# P07-LCD.net
KiCad netlist of a schematic drawn in Altium Designer
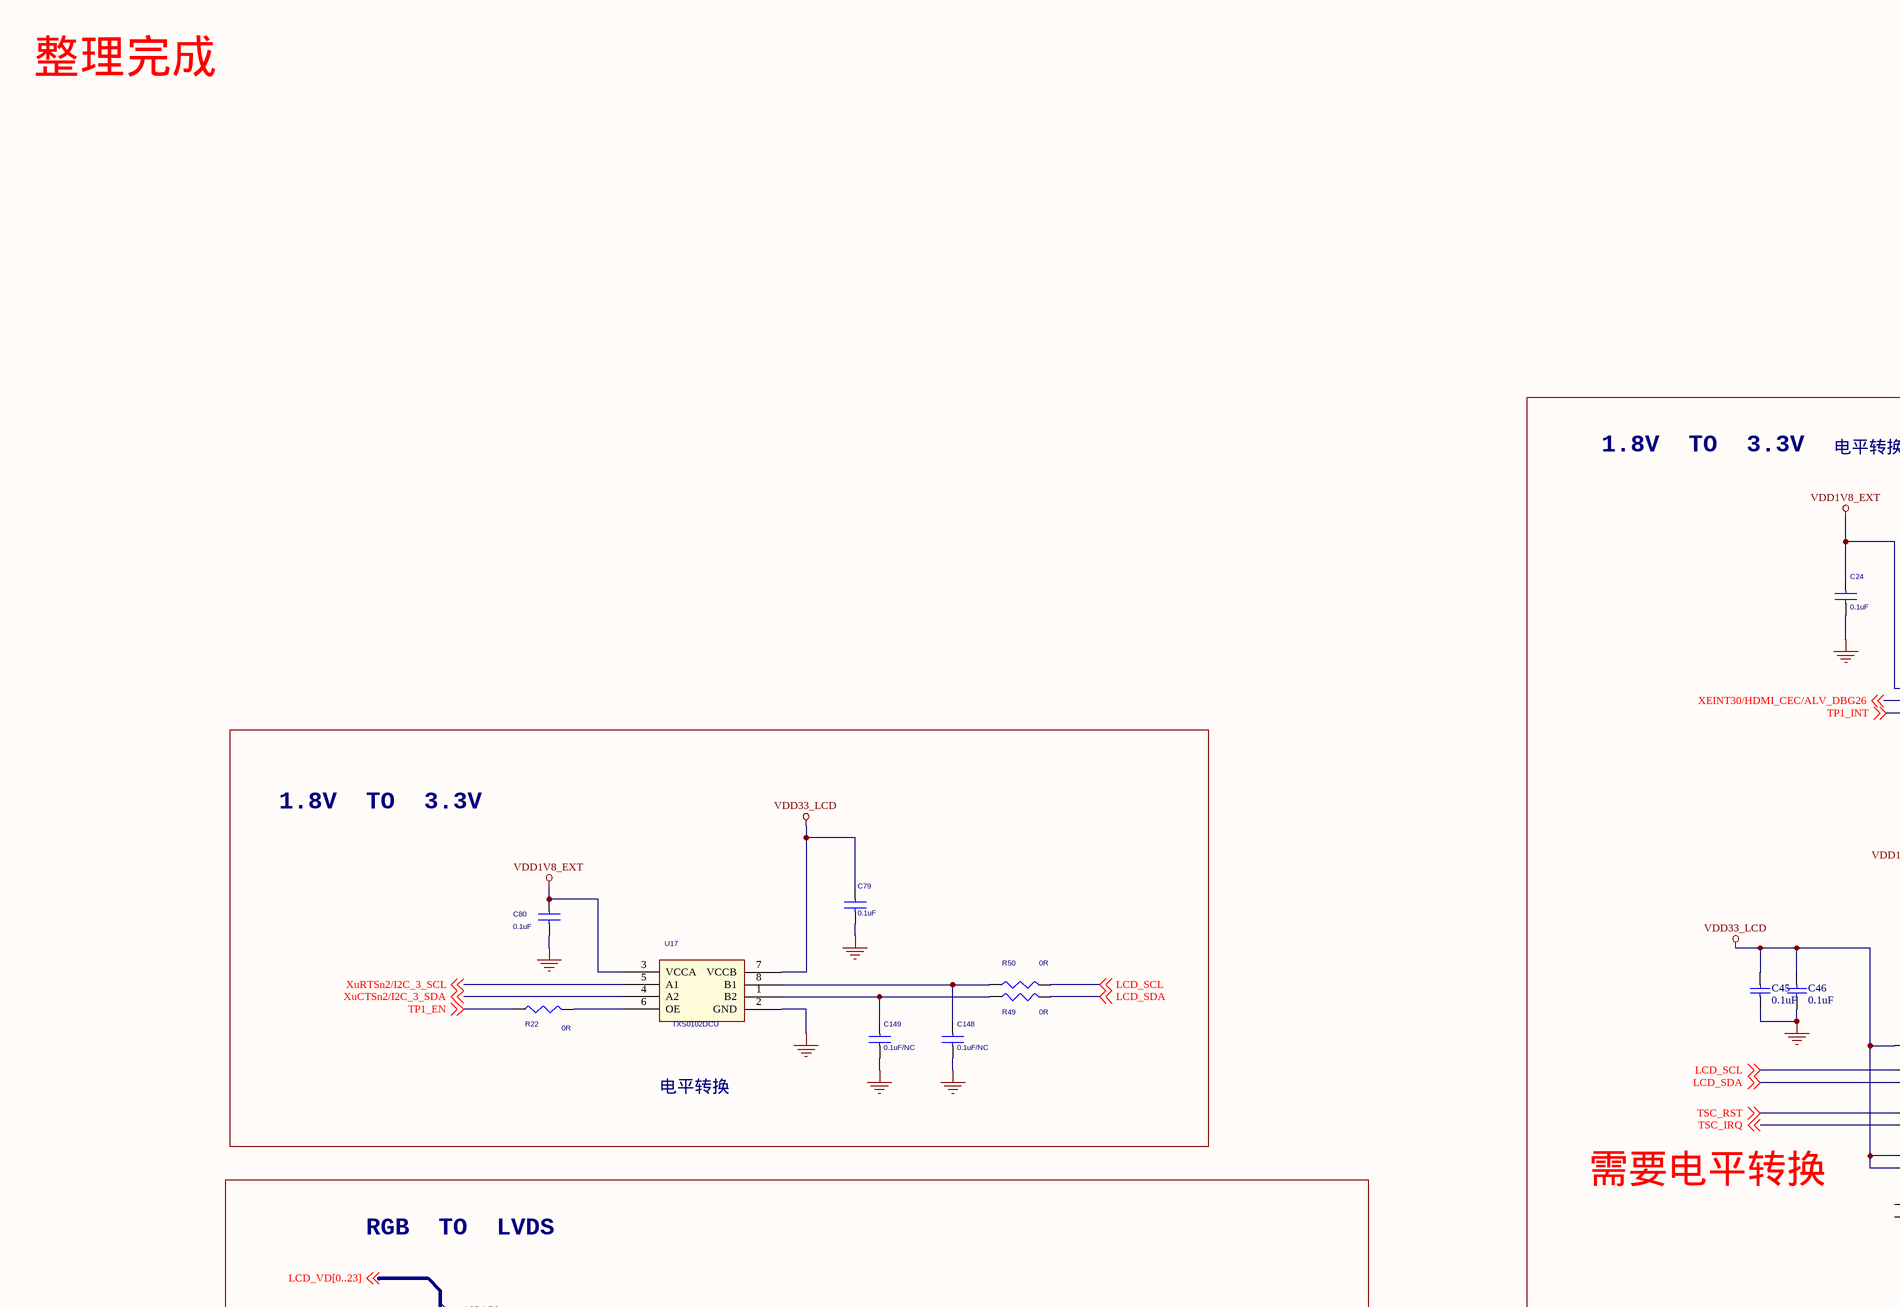
[diagram p0: P07-LCD.SchDoc, top left]
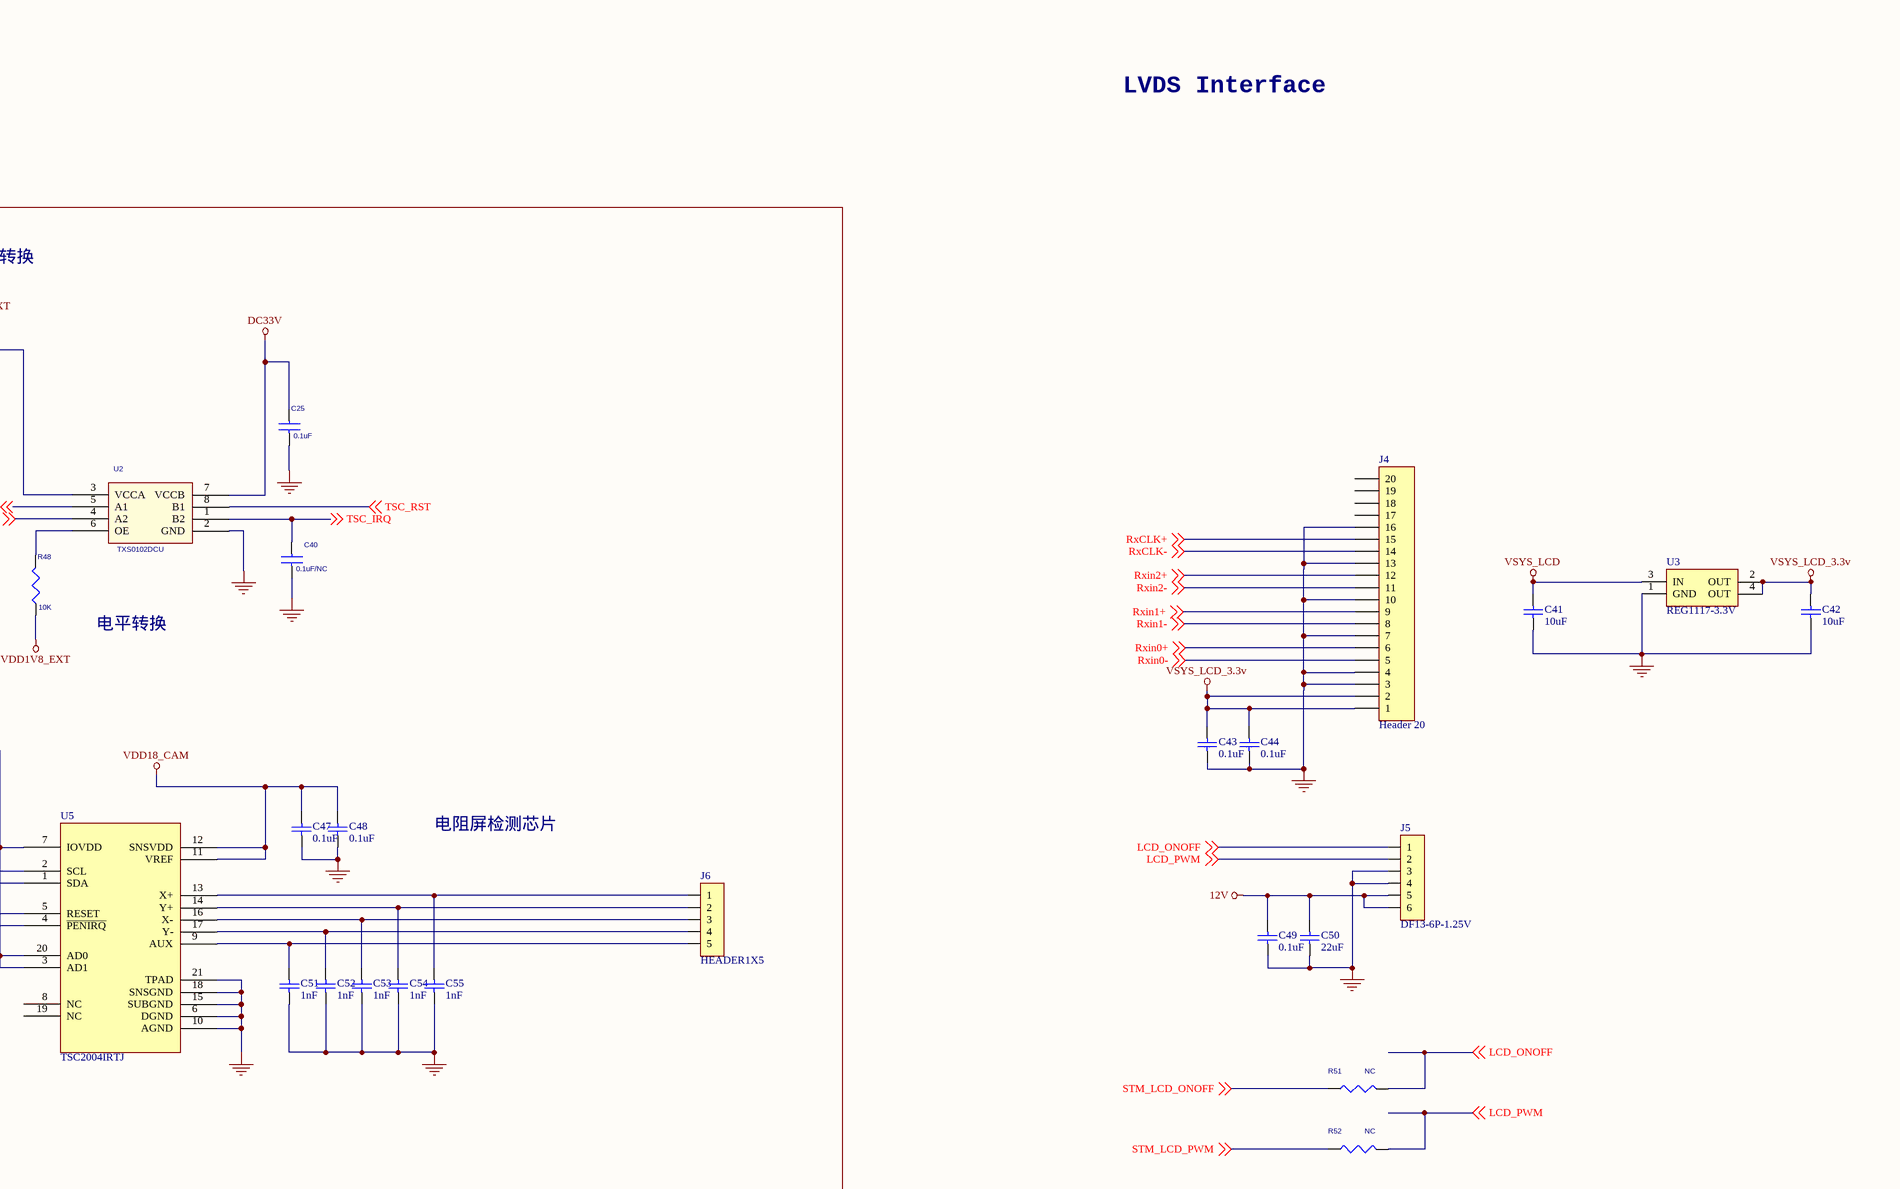
[diagram p1: P07-LCD.SchDoc, top right]
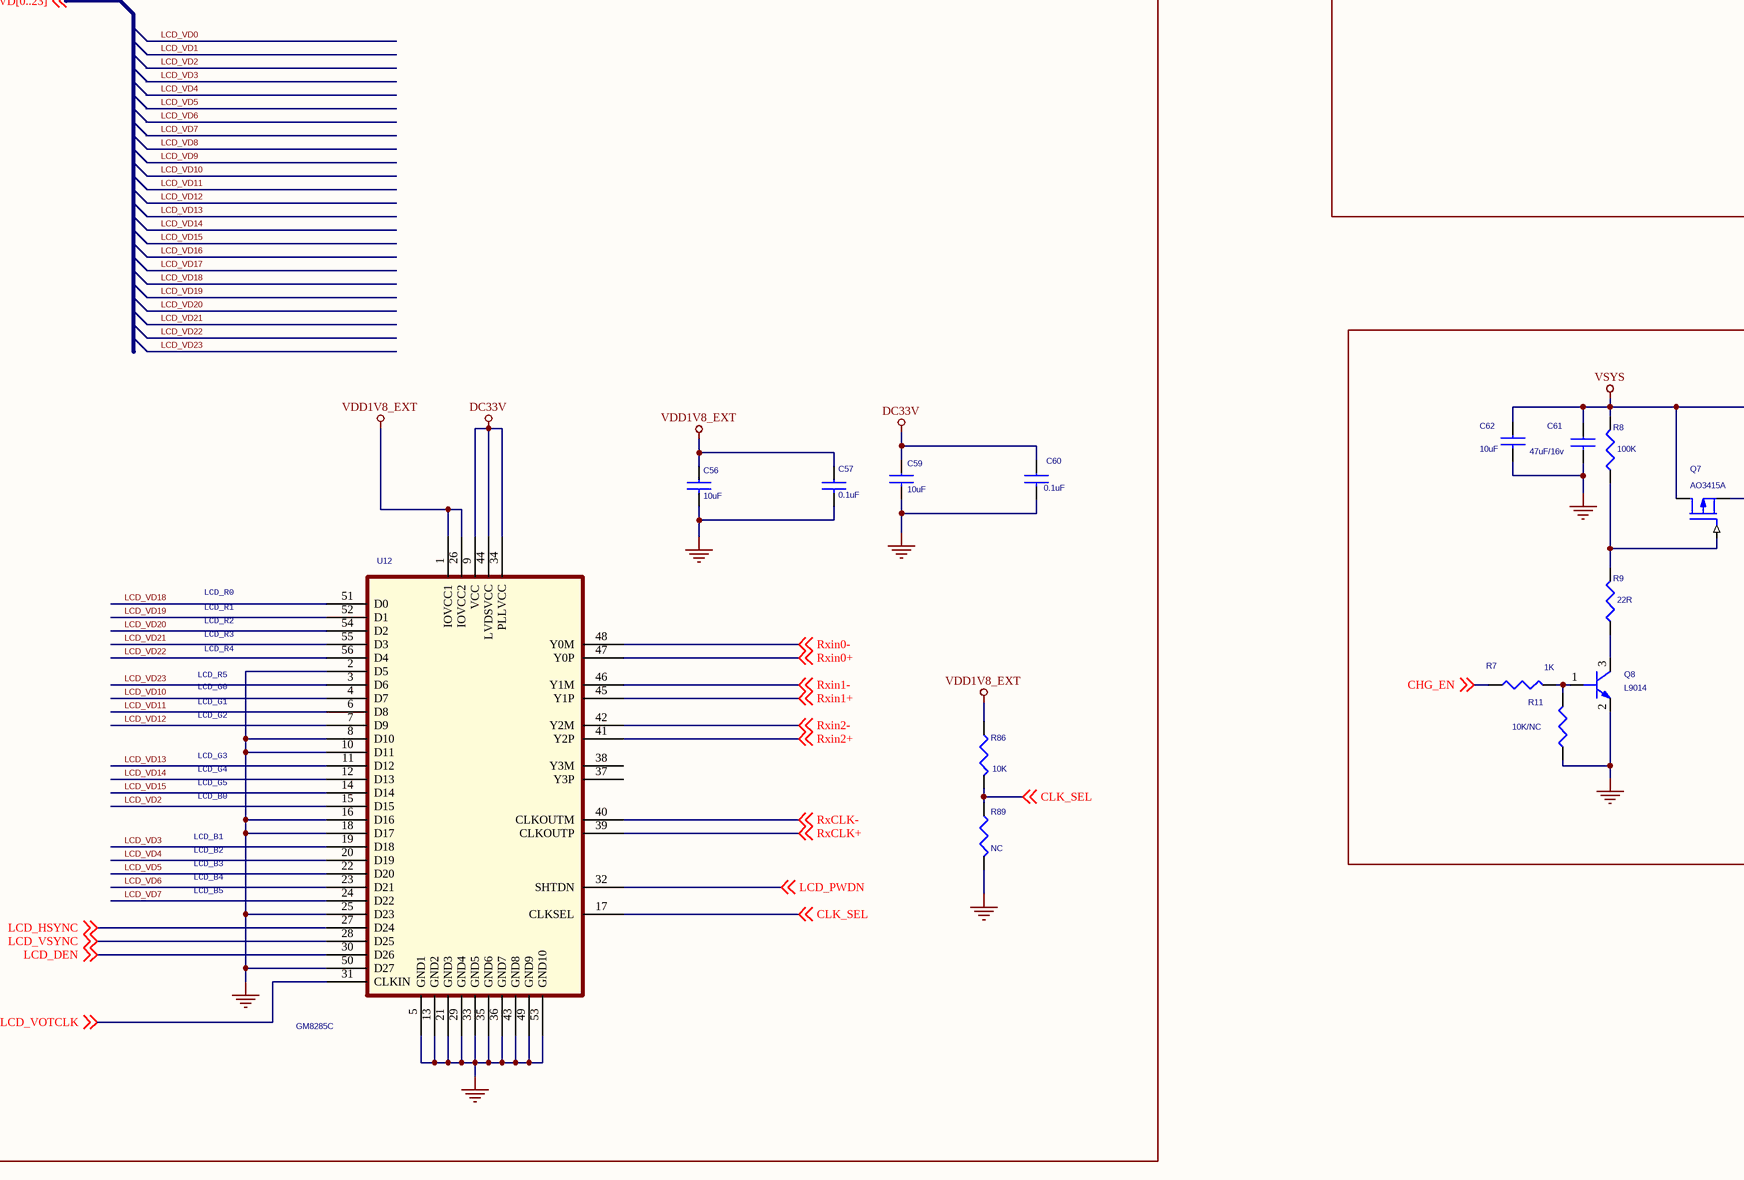
[diagram p2: P07-LCD.SchDoc, bottom left]
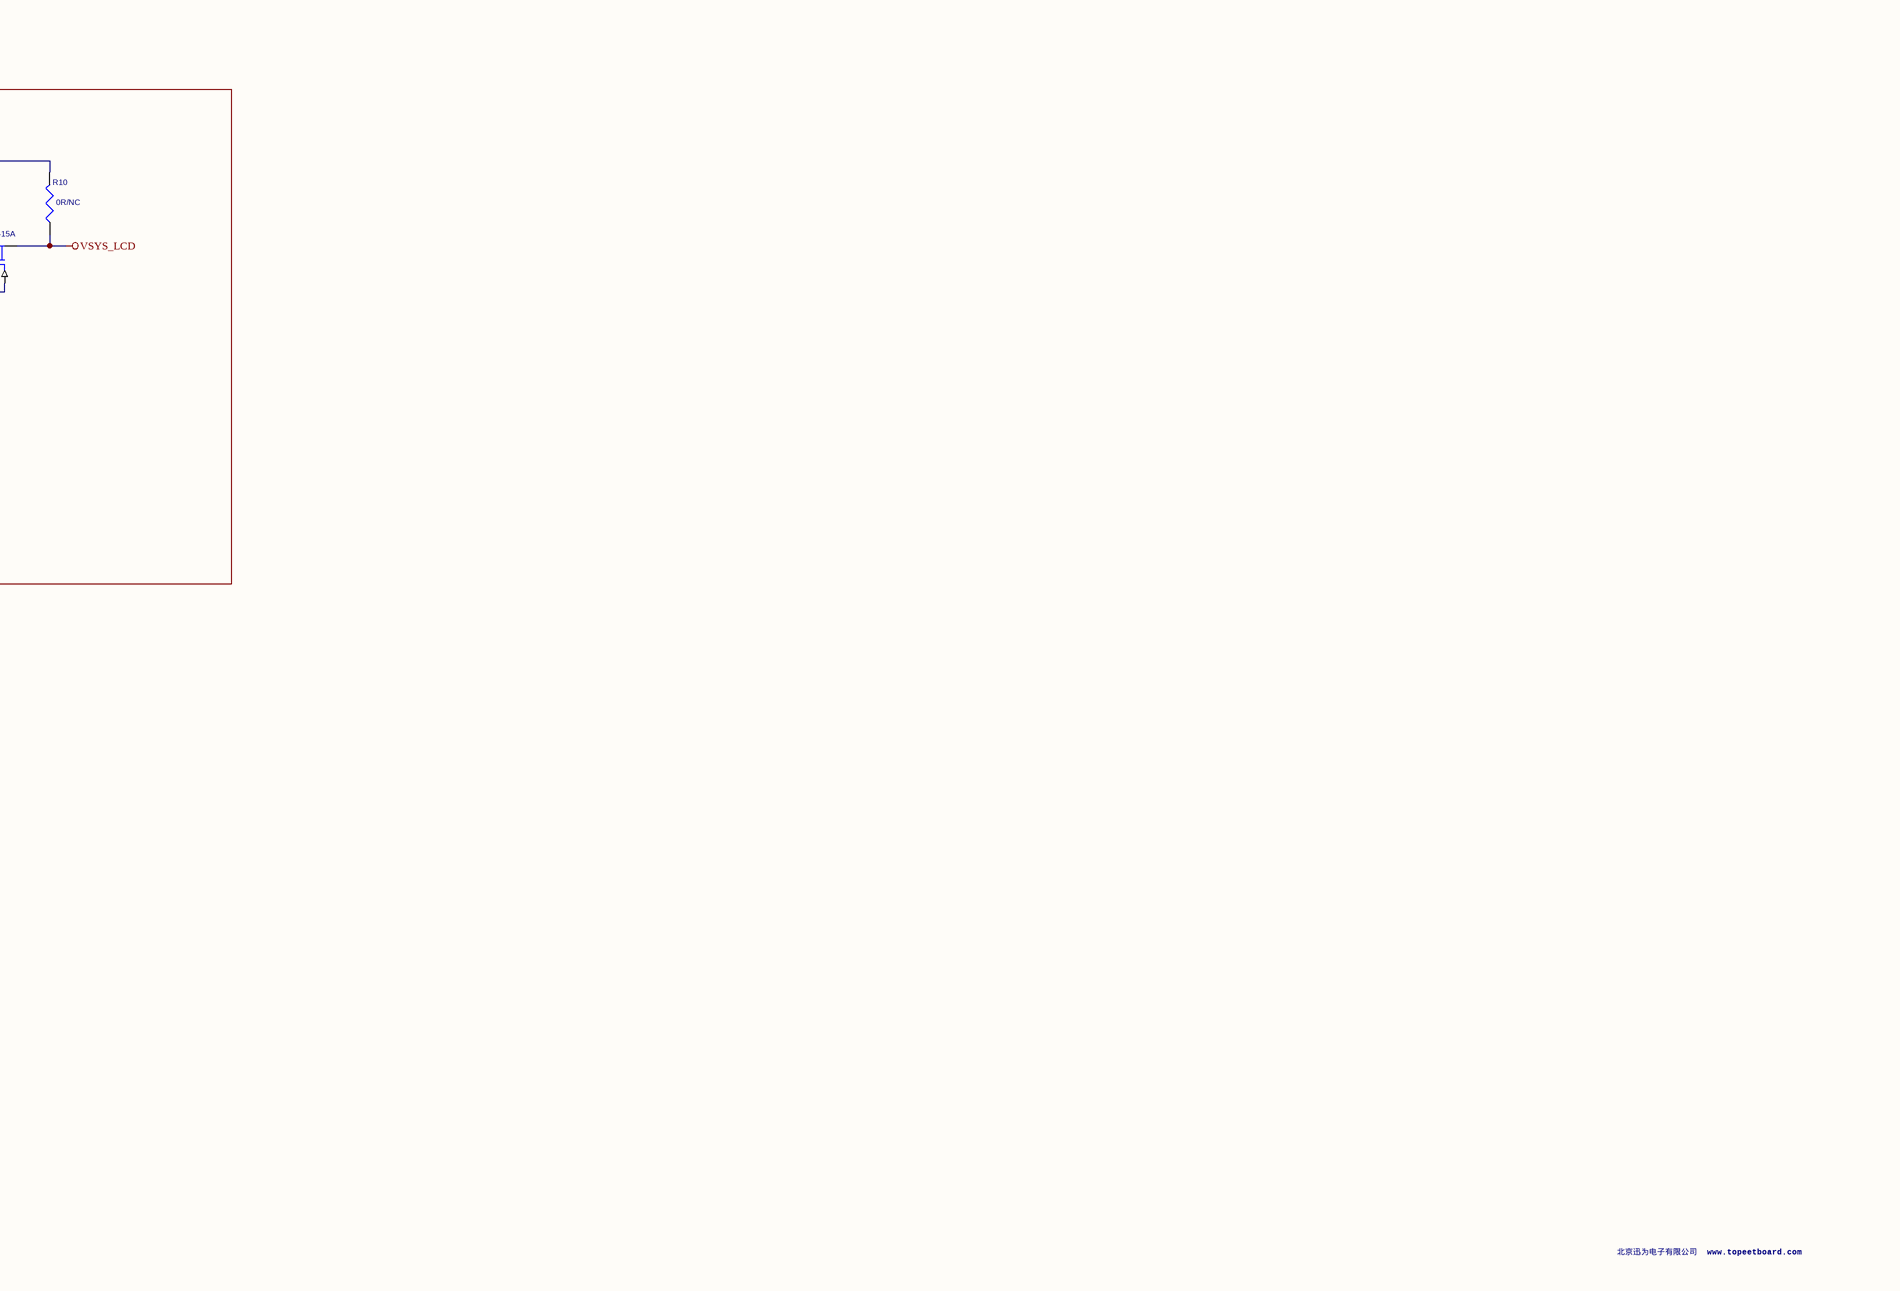
[diagram p3: P07-LCD.SchDoc, bottom right]

(export (version "E")
  (design (tool "Eeschema 10.0.6"))
  (components
    (comp (ref "C24") (value "0.1uF") (footprint "C0603-S") (libsource (lib "*") (part "C0603_0")))
    (comp (ref "C25") (value "0.1uF") (footprint "C0603-S") (libsource (lib "*") (part "C0603_0")))
    (comp (ref "C40") (value "0.1uF/NC") (footprint "C0603-S") (libsource (lib "*") (part "C0603_0")))
    (comp (ref "C41")
      (value "10uF")
      (footprint "C0603-s")
      (description "CAP")
      (fields (field (name "PUBLISHER") "Altium Limited"))
      (libsource (lib "Passive Components Class") (part "CAP"))
    )
    (comp (ref "C42")
      (value "10uF")
      (footprint "C0603-s")
      (description "CAP")
      (fields (field (name "PUBLISHER") "Altium Limited"))
      (libsource (lib "Passive Components Class") (part "CAP"))
    )
    (comp (ref "C43")
      (value "0.1uF")
      (footprint "C0603-s")
      (description "CAP")
      (fields (field (name "PUBLISHER") "Altium Limited"))
      (libsource (lib "Passive Components Class") (part "CAP"))
    )
    (comp (ref "C44")
      (value "0.1uF")
      (footprint "C0603-s")
      (description "CAP")
      (fields (field (name "PUBLISHER") "Altium Limited"))
      (libsource (lib "Passive Components Class") (part "CAP"))
    )
    (comp (ref "C45") (value "0.1uF") (footprint "C0603-S") (libsource (lib "RLCYDF") (part "Cap Semi")))
    (comp (ref "C46") (value "0.1uF") (footprint "C0603-S") (libsource (lib "RLCYDF") (part "Cap Semi")))
    (comp (ref "C47") (value "0.1uF") (footprint "C0603-S") (libsource (lib "RLCYDF") (part "Cap Semi")))
    (comp (ref "C48") (value "0.1uF") (footprint "C0603-S") (libsource (lib "RLCYDF") (part "Cap Semi")))
    (comp (ref "C49")
      (value "0.1uF")
      (footprint "C0603-s")
      (description "CAP")
      (fields (field (name "PUBLISHER") "Altium Limited"))
      (libsource (lib "Passive Components Class") (part "CAP"))
    )
    (comp (ref "C50")
      (value "22uF")
      (footprint "C0805-s")
      (description "CAP")
      (fields (field (name "PUBLISHER") "Altium Limited"))
      (libsource (lib "Passive Components Class") (part "CAP"))
    )
    (comp (ref "C51") (value "1nF") (footprint "C0603-S") (libsource (lib "RLCYDF") (part "Cap Semi")))
    (comp (ref "C52") (value "1nF") (footprint "C0603-S") (libsource (lib "RLCYDF") (part "Cap Semi")))
    (comp (ref "C53") (value "1nF") (footprint "C0603-S") (libsource (lib "RLCYDF") (part "Cap Semi")))
    (comp (ref "C54") (value "1nF") (footprint "C0603-S") (libsource (lib "RLCYDF") (part "Cap Semi")))
    (comp (ref "C55") (value "1nF") (footprint "C0603-S") (libsource (lib "RLCYDF") (part "Cap Semi")))
    (comp (ref "C56") (value "10uF") (footprint "C0805-S") (libsource (lib "*") (part "C1608_Dup2")))
    (comp (ref "C57") (value "0.1uF") (footprint "C0603-S") (libsource (lib "*") (part "C0402_0")))
    (comp (ref "C59") (value "10uF") (footprint "C0805-S") (libsource (lib "*") (part "C1608_Dup2")))
    (comp (ref "C60") (value "0.1uF") (footprint "C0603-S") (libsource (lib "*") (part "C0402_0")))
    (comp (ref "C61") (value "47uF/16v") (footprint "C1206-S") (libsource (lib "*") (part "C1608_Dup2")))
    (comp (ref "C62") (value "10uF") (footprint "C0805-S") (libsource (lib "*") (part "C1608_Dup2")))
    (comp (ref "C79") (value "0.1uF") (footprint "C0603-S") (libsource (lib "*") (part "C0603_0")))
    (comp (ref "C80") (value "0.1uF") (footprint "C0603-S") (libsource (lib "*") (part "C0603_0")))
    (comp (ref "C148") (value "0.1uF/NC") (footprint "C0603-S") (libsource (lib "*") (part "C0402_0")))
    (comp (ref "C149") (value "0.1uF/NC") (footprint "C0603-S") (libsource (lib "*") (part "C0402_0")))
    (comp (ref "J4")
      (value "Header 20")
      (footprint "DF19G-20P")
      (description "Header, 20-Pin")
      (fields (field (name "PUBLISHER") "Altium Limited"))
      (libsource (lib "Miscellaneous Connectors") (part "Header 20"))
    )
    (comp (ref "J5")
      (value "DF13-6P-1.25V")
      (footprint "DF13-6P-1.25V")
      (libsource (lib "Connector Class") (part "HEADER1X6"))
    )
    (comp (ref "J6")
      (value "HEADER1X5")
      (footprint "FFC/SM1.0-5")
      (libsource (lib "Connector Class") (part "HEADER1X5"))
    )
    (comp (ref "Q7") (value "AO3415A") (libsource (lib "*") (part "MOSFET P")))
    (comp (ref "Q8") (value "L9014") (libsource (lib "*") (part "L14P2/TO_1")))
    (comp (ref "R7") (value "1K") (footprint "R0603-S") (libsource (lib "*") (part "R1005_0_Dup1")))
    (comp (ref "R8") (value "100K") (footprint "R0603-S") (libsource (lib "*") (part "R1005_0_Dup1")))
    (comp (ref "R9") (value "22R") (footprint "R0603-S") (libsource (lib "*") (part "R1005_0_Dup1")))
    (comp (ref "R10") (value "0R/NC") (footprint "R0603-S") (libsource (lib "*") (part "R1005_0_Dup1")))
    (comp (ref "R11") (value "10K/NC") (footprint "R0603-S") (libsource (lib "*") (part "R1005_0_Dup1")))
    (comp (ref "R22") (value "0R") (footprint "R0603-S") (libsource (lib "*") (part "R1005_0_Dup1")))
    (comp (ref "R48") (value "10K") (footprint "R0603-S") (libsource (lib "*") (part "R0603_0")))
    (comp (ref "R49") (value "0R") (footprint "R0603-S") (libsource (lib "*") (part "R1005_0_Dup1")))
    (comp (ref "R50") (value "0R") (footprint "R0603-S") (libsource (lib "*") (part "R1005_0_Dup1")))
    (comp (ref "R51") (value "NC") (footprint "R0603-S") (libsource (lib "*") (part "R1005_0_Dup1")))
    (comp (ref "R52") (value "NC") (footprint "R0603-S") (libsource (lib "*") (part "R1005_0_Dup1")))
    (comp (ref "R86") (value "10K") (footprint "R0603-S") (libsource (lib "*") (part "R1005_0_Dup1")))
    (comp (ref "R89") (value "NC") (footprint "R0603-S") (libsource (lib "*") (part "R1005_0_Dup1")))
    (comp (ref "U2") (value "TXS0102DCU") (libsource (lib "*") (part "TXS0102DCU_1")))
    (comp (ref "U3")
      (value "REG1117-3.3V")
      (footprint "SOT-223")
      (description "800mA and 1A Low Dropout Positive Regulator 2.85V, 3.3V, 5V, and Adjustable")
      (fields (field (name "PUBLISHER") "Altium Limited"))
      (libsource (lib "BB Power Mgt Voltage Regulator") (part "REG1117-3.3"))
    )
    (comp (ref "U5")
      (value "TSC2004IRTJ")
      (footprint "QFN20")
      (description "Current Sensor")
      (libsource (lib "Sensor Class") (part "TSC2004IRTJ"))
    )
    (comp (ref "U12")
      (value "GM8285C")
      (footprint "TSSOP56")
      (libsource (lib "*") (part "U-SN75LVDS83BDGG_3"))
    )
    (comp (ref "U17") (value "TXS0102DCU") (libsource (lib "*") (part "TXS0102DCU_1")))
  )
  (nets
    (net (code "1") (name "12V") (class "Default")
      (node (ref "C49") (pin "2") (pinfunction "2_2") (pintype "passive"))
      (node (ref "C50") (pin "2") (pinfunction "2_2") (pintype "passive"))
      (node (ref "J5") (pin "5") (pinfunction "5_5") (pintype "passive"))
      (node (ref "J5") (pin "6") (pinfunction "6_6") (pintype "passive"))
    )
    (net (code "2") (name "CHG_EN") (class "Default")
      (node (ref "R7") (pin "2") (pinfunction "2_2") (pintype "passive"))
    )
    (net (code "3") (name "CLK_SEL") (class "Default")
      (node (ref "R86") (pin "2") (pinfunction "2_2") (pintype "passive"))
      (node (ref "R89") (pin "1") (pinfunction "1_1") (pintype "passive"))
      (node (ref "U12") (pin "17") (pinfunction "CLKSEL_17") (pintype "passive"))
    )
    (net (code "4") (name "DC33V") (class "Default")
      (node (ref "C25") (pin "1") (pinfunction "1_1") (pintype "passive"))
      (node (ref "C59") (pin "1") (pinfunction "1_1") (pintype "passive"))
      (node (ref "C60") (pin "1") (pinfunction "1_1") (pintype "passive"))
      (node (ref "U12") (pin "34") (pinfunction "PLLVCC_34") (pintype "passive"))
      (node (ref "U12") (pin "44") (pinfunction "LVDSVCC_44") (pintype "passive"))
      (node (ref "U12") (pin "9") (pinfunction "VCC_9") (pintype "passive"))
      (node (ref "U2") (pin "7") (pinfunction "VCCB_7") (pintype "passive"))
    )
    (net (code "5") (name "GND") (class "Default")
      (node (ref "C148") (pin "2") (pinfunction "2_2") (pintype "passive"))
      (node (ref "C149") (pin "2") (pinfunction "2_2") (pintype "passive"))
      (node (ref "C24") (pin "2") (pinfunction "2_2") (pintype "passive"))
      (node (ref "C25") (pin "2") (pinfunction "2_2") (pintype "passive"))
      (node (ref "C40") (pin "2") (pinfunction "2_2") (pintype "passive"))
      (node (ref "C41") (pin "1") (pinfunction "1_1") (pintype "passive"))
      (node (ref "C42") (pin "1") (pinfunction "1_1") (pintype "passive"))
      (node (ref "C43") (pin "1") (pinfunction "1_1") (pintype "passive"))
      (node (ref "C44") (pin "1") (pinfunction "1_1") (pintype "passive"))
      (node (ref "C45") (pin "1") (pinfunction "1_1") (pintype "passive"))
      (node (ref "C46") (pin "1") (pinfunction "1_1") (pintype "passive"))
      (node (ref "C47") (pin "1") (pinfunction "1_1") (pintype "passive"))
      (node (ref "C48") (pin "1") (pinfunction "1_1") (pintype "passive"))
      (node (ref "C49") (pin "1") (pinfunction "1_1") (pintype "passive"))
      (node (ref "C50") (pin "1") (pinfunction "1_1") (pintype "passive"))
      (node (ref "C51") (pin "1") (pinfunction "1_1") (pintype "passive"))
      (node (ref "C52") (pin "1") (pinfunction "1_1") (pintype "passive"))
      (node (ref "C53") (pin "1") (pinfunction "1_1") (pintype "passive"))
      (node (ref "C54") (pin "1") (pinfunction "1_1") (pintype "passive"))
      (node (ref "C55") (pin "1") (pinfunction "1_1") (pintype "passive"))
      (node (ref "C56") (pin "2") (pinfunction "2_2") (pintype "passive"))
      (node (ref "C57") (pin "2") (pinfunction "2_2") (pintype "passive"))
      (node (ref "C59") (pin "2") (pinfunction "2_2") (pintype "passive"))
      (node (ref "C60") (pin "2") (pinfunction "2_2") (pintype "passive"))
      (node (ref "C61") (pin "2") (pinfunction "2_2") (pintype "passive"))
      (node (ref "C62") (pin "2") (pinfunction "2_2") (pintype "passive"))
      (node (ref "C79") (pin "2") (pinfunction "2_2") (pintype "passive"))
      (node (ref "C80") (pin "2") (pinfunction "2_2") (pintype "passive"))
      (node (ref "J4") (pin "10") (pinfunction "10_10") (pintype "passive"))
      (node (ref "J4") (pin "13") (pinfunction "13_13") (pintype "passive"))
      (node (ref "J4") (pin "16") (pinfunction "16_16") (pintype "passive"))
      (node (ref "J4") (pin "3") (pinfunction "3_3") (pintype "passive"))
      (node (ref "J4") (pin "4") (pinfunction "4_4") (pintype "passive"))
      (node (ref "J4") (pin "7") (pinfunction "7_7") (pintype "passive"))
      (node (ref "J5") (pin "3") (pinfunction "3_3") (pintype "passive"))
      (node (ref "J5") (pin "4") (pinfunction "4_4") (pintype "passive"))
      (node (ref "Q8") (pin "2") (pinfunction "EMITTER_2") (pintype "passive"))
      (node (ref "R11") (pin "2") (pinfunction "2_2") (pintype "passive"))
      (node (ref "R89") (pin "2") (pinfunction "2_2") (pintype "passive"))
      (node (ref "U12") (pin "10") (pinfunction "D11_10") (pintype "passive"))
      (node (ref "U12") (pin "13") (pinfunction "GND2_13") (pintype "passive"))
      (node (ref "U12") (pin "16") (pinfunction "D16_16") (pintype "passive"))
      (node (ref "U12") (pin "18") (pinfunction "D17_18") (pintype "passive"))
      (node (ref "U12") (pin "2") (pinfunction "D5_2") (pintype "passive"))
      (node (ref "U12") (pin "21") (pinfunction "GND3_21") (pintype "passive"))
      (node (ref "U12") (pin "25") (pinfunction "D23_25") (pintype "passive"))
      (node (ref "U12") (pin "29") (pinfunction "GND4_29") (pintype "passive"))
      (node (ref "U12") (pin "33") (pinfunction "GND5_33") (pintype "passive"))
      (node (ref "U12") (pin "35") (pinfunction "GND6_35") (pintype "passive"))
      (node (ref "U12") (pin "36") (pinfunction "GND7_36") (pintype "passive"))
      (node (ref "U12") (pin "43") (pinfunction "GND8_43") (pintype "passive"))
      (node (ref "U12") (pin "49") (pinfunction "GND9_49") (pintype "passive"))
      (node (ref "U12") (pin "5") (pinfunction "GND1_5") (pintype "passive"))
      (node (ref "U12") (pin "50") (pinfunction "D27_50") (pintype "passive"))
      (node (ref "U12") (pin "53") (pinfunction "GND10_53") (pintype "passive"))
      (node (ref "U12") (pin "8") (pinfunction "D10_8") (pintype "passive"))
      (node (ref "U17") (pin "2") (pinfunction "GND_2") (pintype "passive"))
      (node (ref "U2") (pin "2") (pinfunction "GND_2") (pintype "passive"))
      (node (ref "U3") (pin "1") (pinfunction "GND_1") (pintype "power_in"))
      (node (ref "U5") (pin "10") (pinfunction "AGND_10") (pintype "passive"))
      (node (ref "U5") (pin "15") (pinfunction "SUBGND_15") (pintype "passive"))
      (node (ref "U5") (pin "18") (pinfunction "SNSGND_18") (pintype "passive"))
      (node (ref "U5") (pin "21") (pinfunction "TPAD_21") (pintype "passive"))
      (node (ref "U5") (pin "6") (pinfunction "DGND_6") (pintype "passive"))
    )
    (net (code "6") (name "LCD_DEN") (class "Default")
      (node (ref "U12") (pin "30") (pinfunction "D26_30") (pintype "passive"))
    )
    (net (code "7") (name "LCD_HSYNC") (class "Default")
      (node (ref "U12") (pin "27") (pinfunction "D24_27") (pintype "passive"))
    )
    (net (code "8") (name "LCD_ONOFF") (class "Default")
      (node (ref "J5") (pin "1") (pinfunction "1_1") (pintype "passive"))
      (node (ref "R51") (pin "2") (pinfunction "2_2") (pintype "passive"))
    )
    (net (code "9") (name "LCD_PWDN") (class "Default")
      (node (ref "U12") (pin "32") (pinfunction "SHTDN_32") (pintype "passive"))
    )
    (net (code "10") (name "LCD_PWM") (class "Default")
      (node (ref "J5") (pin "2") (pinfunction "2_2") (pintype "passive"))
      (node (ref "R52") (pin "2") (pinfunction "2_2") (pintype "passive"))
    )
    (net (code "11") (name "LCD_SCL") (class "Default")
      (node (ref "R50") (pin "2") (pinfunction "2_2") (pintype "passive"))
      (node (ref "U5") (pin "2") (pinfunction "SCL_2") (pintype "passive"))
    )
    (net (code "12") (name "LCD_SDA") (class "Default")
      (node (ref "R49") (pin "2") (pinfunction "2_2") (pintype "passive"))
      (node (ref "U5") (pin "1") (pinfunction "SDA_1") (pintype "passive"))
    )
    (net (code "15") (name "LCD_VD2") (class "Default")
      (node (ref "U12") (pin "15") (pinfunction "D15_15") (pintype "passive"))
    )
    (net (code "16") (name "LCD_VD3") (class "Default")
      (node (ref "U12") (pin "19") (pinfunction "D18_19") (pintype "passive"))
    )
    (net (code "17") (name "LCD_VD4") (class "Default")
      (node (ref "U12") (pin "20") (pinfunction "D19_20") (pintype "passive"))
    )
    (net (code "18") (name "LCD_VD5") (class "Default")
      (node (ref "U12") (pin "22") (pinfunction "D20_22") (pintype "passive"))
    )
    (net (code "19") (name "LCD_VD6") (class "Default")
      (node (ref "U12") (pin "23") (pinfunction "D21_23") (pintype "passive"))
    )
    (net (code "20") (name "LCD_VD7") (class "Default")
      (node (ref "U12") (pin "24") (pinfunction "D22_24") (pintype "passive"))
    )
    (net (code "23") (name "LCD_VD10") (class "Default")
      (node (ref "U12") (pin "4") (pinfunction "D7_4") (pintype "passive"))
    )
    (net (code "24") (name "LCD_VD11") (class "Default")
      (node (ref "U12") (pin "6") (pinfunction "D8_6") (pintype "passive"))
    )
    (net (code "25") (name "LCD_VD12") (class "Default")
      (node (ref "U12") (pin "7") (pinfunction "D9_7") (pintype "passive"))
    )
    (net (code "26") (name "LCD_VD13") (class "Default")
      (node (ref "U12") (pin "11") (pinfunction "D12_11") (pintype "passive"))
    )
    (net (code "27") (name "LCD_VD14") (class "Default")
      (node (ref "U12") (pin "12") (pinfunction "D13_12") (pintype "passive"))
    )
    (net (code "28") (name "LCD_VD15") (class "Default")
      (node (ref "U12") (pin "14") (pinfunction "D14_14") (pintype "passive"))
    )
    (net (code "31") (name "LCD_VD18") (class "Default")
      (node (ref "U12") (pin "51") (pinfunction "D0_51") (pintype "passive"))
    )
    (net (code "32") (name "LCD_VD19") (class "Default")
      (node (ref "U12") (pin "52") (pinfunction "D1_52") (pintype "passive"))
    )
    (net (code "33") (name "LCD_VD20") (class "Default")
      (node (ref "U12") (pin "54") (pinfunction "D2_54") (pintype "passive"))
    )
    (net (code "34") (name "LCD_VD21") (class "Default")
      (node (ref "U12") (pin "55") (pinfunction "D3_55") (pintype "passive"))
    )
    (net (code "35") (name "LCD_VD22") (class "Default")
      (node (ref "U12") (pin "56") (pinfunction "D4_56") (pintype "passive"))
    )
    (net (code "36") (name "LCD_VD23") (class "Default")
      (node (ref "U12") (pin "3") (pinfunction "D6_3") (pintype "passive"))
    )
    (net (code "38") (name "LCD_VOTCLK") (class "Default")
      (node (ref "U12") (pin "31") (pinfunction "CLKIN_31") (pintype "passive"))
    )
    (net (code "39") (name "LCD_VSYNC") (class "Default")
      (node (ref "U12") (pin "28") (pinfunction "D25_28") (pintype "passive"))
    )
    (net (code "40") (name "Net-(Q7-GATE)") (class "Default")
      (node (ref "Q7") (pin "1") (pinfunction "GATE_1") (pintype "input"))
      (node (ref "R8") (pin "2") (pinfunction "2_2") (pintype "passive"))
      (node (ref "R9") (pin "1") (pinfunction "1_1") (pintype "passive"))
    )
    (net (code "41") (name "Net-(Q8-BASE)") (class "Default")
      (node (ref "Q8") (pin "1") (pinfunction "BASE_1") (pintype "passive"))
      (node (ref "R11") (pin "1") (pinfunction "1_1") (pintype "passive"))
      (node (ref "R7") (pin "1") (pinfunction "1_1") (pintype "passive"))
    )
    (net (code "42") (name "Net-(Q8-COLLECTOR)") (class "Default")
      (node (ref "Q8") (pin "3") (pinfunction "COLLECTOR_3") (pintype "passive"))
      (node (ref "R9") (pin "2") (pinfunction "2_2") (pintype "passive"))
    )
    (net (code "43") (name "Net-(U2-OE)") (class "Default")
      (node (ref "R48") (pin "2") (pinfunction "2_2") (pintype "passive"))
      (node (ref "U2") (pin "6") (pinfunction "OE_6") (pintype "passive"))
    )
    (net (code "44") (name "Net-(U5-AUX)") (class "Default")
      (node (ref "C51") (pin "2") (pinfunction "2_2") (pintype "passive"))
      (node (ref "J6") (pin "5") (pinfunction "5_5") (pintype "passive"))
      (node (ref "U5") (pin "9") (pinfunction "AUX_9") (pintype "passive"))
    )
    (net (code "45") (name "Net-(U5-X+)") (class "Default")
      (node (ref "C55") (pin "2") (pinfunction "2_2") (pintype "passive"))
      (node (ref "J6") (pin "1") (pinfunction "1_1") (pintype "passive"))
      (node (ref "U5") (pin "13") (pinfunction "X+_13") (pintype "passive"))
    )
    (net (code "46") (name "Net-(U5-X-)") (class "Default")
      (node (ref "C53") (pin "2") (pinfunction "2_2") (pintype "passive"))
      (node (ref "J6") (pin "3") (pinfunction "3_3") (pintype "passive"))
      (node (ref "U5") (pin "16") (pinfunction "X-_16") (pintype "passive"))
    )
    (net (code "47") (name "Net-(U5-Y+)") (class "Default")
      (node (ref "C54") (pin "2") (pinfunction "2_2") (pintype "passive"))
      (node (ref "J6") (pin "2") (pinfunction "2_2") (pintype "passive"))
      (node (ref "U5") (pin "14") (pinfunction "Y+_14") (pintype "passive"))
    )
    (net (code "48") (name "Net-(U5-Y-)") (class "Default")
      (node (ref "C52") (pin "2") (pinfunction "2_2") (pintype "passive"))
      (node (ref "J6") (pin "4") (pinfunction "4_4") (pintype "passive"))
      (node (ref "U5") (pin "17") (pinfunction "Y-_17") (pintype "passive"))
    )
    (net (code "49") (name "Net-(U17-B1)") (class "Default")
      (node (ref "C148") (pin "1") (pinfunction "1_1") (pintype "passive"))
      (node (ref "R50") (pin "1") (pinfunction "1_1") (pintype "passive"))
      (node (ref "U17") (pin "8") (pinfunction "B1_8") (pintype "passive"))
    )
    (net (code "50") (name "Net-(U17-B2)") (class "Default")
      (node (ref "C149") (pin "1") (pinfunction "1_1") (pintype "passive"))
      (node (ref "R49") (pin "1") (pinfunction "1_1") (pintype "passive"))
      (node (ref "U17") (pin "1") (pinfunction "B2_1") (pintype "passive"))
    )
    (net (code "51") (name "Net-(U17-OE)") (class "Default")
      (node (ref "R22") (pin "2") (pinfunction "2_2") (pintype "passive"))
      (node (ref "U17") (pin "6") (pinfunction "OE_6") (pintype "passive"))
    )
    (net (code "52") (name "RxCLK+") (class "Default")
      (node (ref "J4") (pin "15") (pinfunction "15_15") (pintype "passive"))
      (node (ref "U12") (pin "39") (pinfunction "CLKOUTP_39") (pintype "passive"))
    )
    (net (code "53") (name "RxCLK-") (class "Default")
      (node (ref "J4") (pin "14") (pinfunction "14_14") (pintype "passive"))
      (node (ref "U12") (pin "40") (pinfunction "CLKOUTM_40") (pintype "passive"))
    )
    (net (code "54") (name "Rxin0+") (class "Default")
      (node (ref "J4") (pin "6") (pinfunction "6_6") (pintype "passive"))
      (node (ref "U12") (pin "47") (pinfunction "Y0P_47") (pintype "passive"))
    )
    (net (code "55") (name "Rxin0-") (class "Default")
      (node (ref "J4") (pin "5") (pinfunction "5_5") (pintype "passive"))
      (node (ref "U12") (pin "48") (pinfunction "Y0M_48") (pintype "passive"))
    )
    (net (code "56") (name "Rxin1+") (class "Default")
      (node (ref "J4") (pin "9") (pinfunction "9_9") (pintype "passive"))
      (node (ref "U12") (pin "45") (pinfunction "Y1P_45") (pintype "passive"))
    )
    (net (code "57") (name "Rxin1-") (class "Default")
      (node (ref "J4") (pin "8") (pinfunction "8_8") (pintype "passive"))
      (node (ref "U12") (pin "46") (pinfunction "Y1M_46") (pintype "passive"))
    )
    (net (code "58") (name "Rxin2+") (class "Default")
      (node (ref "J4") (pin "12") (pinfunction "12_12") (pintype "passive"))
      (node (ref "U12") (pin "41") (pinfunction "Y2P_41") (pintype "passive"))
    )
    (net (code "59") (name "Rxin2-") (class "Default")
      (node (ref "J4") (pin "11") (pinfunction "11_11") (pintype "passive"))
      (node (ref "U12") (pin "42") (pinfunction "Y2M_42") (pintype "passive"))
    )
    (net (code "60") (name "STM_LCD_ONOFF") (class "Default")
      (node (ref "R51") (pin "1") (pinfunction "1_1") (pintype "passive"))
    )
    (net (code "61") (name "STM_LCD_PWM") (class "Default")
      (node (ref "R52") (pin "1") (pinfunction "1_1") (pintype "passive"))
    )
    (net (code "62") (name "TP1_EN") (class "Default")
      (node (ref "R22") (pin "1") (pinfunction "1_1") (pintype "passive"))
    )
    (net (code "63") (name "TP1_INT") (class "Default")
      (node (ref "U2") (pin "4") (pinfunction "A2_4") (pintype "passive"))
    )
    (net (code "64") (name "TSC_IRQ") (class "Default")
      (node (ref "C40") (pin "1") (pinfunction "1_1") (pintype "passive"))
      (node (ref "U2") (pin "1") (pinfunction "B2_1") (pintype "passive"))
      (node (ref "U5") (pin "4") (pinfunction "~{PENIRQ}_4") (pintype "passive"))
    )
    (net (code "65") (name "TSC_RST") (class "Default")
      (node (ref "U2") (pin "8") (pinfunction "B1_8") (pintype "passive"))
      (node (ref "U5") (pin "5") (pinfunction "RESET_5") (pintype "passive"))
    )
    (net (code "66") (name "VDD1V8_EXT") (class "Default")
      (node (ref "C24") (pin "1") (pinfunction "1_1") (pintype "passive"))
      (node (ref "C56") (pin "1") (pinfunction "1_1") (pintype "passive"))
      (node (ref "C57") (pin "1") (pinfunction "1_1") (pintype "passive"))
      (node (ref "C80") (pin "1") (pinfunction "1_1") (pintype "passive"))
      (node (ref "R48") (pin "1") (pinfunction "1_1") (pintype "passive"))
      (node (ref "R86") (pin "1") (pinfunction "1_1") (pintype "passive"))
      (node (ref "U12") (pin "1") (pinfunction "IOVCC1_1") (pintype "passive"))
      (node (ref "U12") (pin "26") (pinfunction "IOVCC2_26") (pintype "passive"))
      (node (ref "U17") (pin "3") (pinfunction "VCCA_3") (pintype "passive"))
      (node (ref "U2") (pin "3") (pinfunction "VCCA_3") (pintype "passive"))
    )
    (net (code "67") (name "VDD18_CAM") (class "Default")
      (node (ref "C47") (pin "2") (pinfunction "2_2") (pintype "passive"))
      (node (ref "C48") (pin "2") (pinfunction "2_2") (pintype "passive"))
      (node (ref "U5") (pin "11") (pinfunction "VREF_11") (pintype "passive"))
      (node (ref "U5") (pin "12") (pinfunction "SNSVDD_12") (pintype "passive"))
    )
    (net (code "68") (name "VDD33_LCD") (class "Default")
      (node (ref "C45") (pin "2") (pinfunction "2_2") (pintype "passive"))
      (node (ref "C46") (pin "2") (pinfunction "2_2") (pintype "passive"))
      (node (ref "C79") (pin "1") (pinfunction "1_1") (pintype "passive"))
      (node (ref "U17") (pin "7") (pinfunction "VCCB_7") (pintype "passive"))
      (node (ref "U5") (pin "20") (pinfunction "AD0_20") (pintype "passive"))
      (node (ref "U5") (pin "3") (pinfunction "AD1_3") (pintype "passive"))
      (node (ref "U5") (pin "7") (pinfunction "IOVDD_7") (pintype "passive"))
    )
    (net (code "69") (name "VSYS") (class "Default")
      (node (ref "C61") (pin "1") (pinfunction "1_1") (pintype "passive"))
      (node (ref "C62") (pin "1") (pinfunction "1_1") (pintype "passive"))
      (node (ref "Q7") (pin "2") (pinfunction "DRAIN_2") (pintype "passive"))
      (node (ref "R10") (pin "1") (pinfunction "1_1") (pintype "passive"))
      (node (ref "R8") (pin "1") (pinfunction "1_1") (pintype "passive"))
    )
    (net (code "70") (name "VSYS_LCD") (class "Default")
      (node (ref "C41") (pin "2") (pinfunction "2_2") (pintype "passive"))
      (node (ref "Q7") (pin "3") (pinfunction "SOURCE_3") (pintype "passive"))
      (node (ref "R10") (pin "2") (pinfunction "2_2") (pintype "passive"))
      (node (ref "U3") (pin "3") (pinfunction "IN_3") (pintype "power_in"))
    )
    (net (code "71") (name "VSYS_LCD_3.3v") (class "Default")
      (node (ref "C42") (pin "2") (pinfunction "2_2") (pintype "passive"))
      (node (ref "C43") (pin "2") (pinfunction "2_2") (pintype "passive"))
      (node (ref "C44") (pin "2") (pinfunction "2_2") (pintype "passive"))
      (node (ref "J4") (pin "1") (pinfunction "1_1") (pintype "passive"))
      (node (ref "J4") (pin "2") (pinfunction "2_2") (pintype "passive"))
      (node (ref "U3") (pin "2") (pinfunction "OUT_2") (pintype "power_in"))
      (node (ref "U3") (pin "4") (pinfunction "OUT_4") (pintype "power_in"))
    )
    (net (code "72") (name "XEINT30{slash}HDMI_CEC{slash}ALV_DBG26") (class "Default")
      (node (ref "U2") (pin "5") (pinfunction "A1_5") (pintype "passive"))
    )
    (net (code "73") (name "XuCTSn2{slash}I2C_3_SDA") (class "Default")
      (node (ref "U17") (pin "4") (pinfunction "A2_4") (pintype "passive"))
    )
    (net (code "74") (name "XuRTSn2{slash}I2C_3_SCL") (class "Default")
      (node (ref "U17") (pin "5") (pinfunction "A1_5") (pintype "passive"))
    )
    (net (code "75") (name "unconnected-(J4-Pad17)") (class "Default")
      (node (ref "J4") (pin "17") (pinfunction "17_17") (pintype "passive"))
    )
    (net (code "76") (name "unconnected-(J4-Pad18)") (class "Default")
      (node (ref "J4") (pin "18") (pinfunction "18_18") (pintype "passive"))
    )
    (net (code "77") (name "unconnected-(J4-Pad19)") (class "Default")
      (node (ref "J4") (pin "19") (pinfunction "19_19") (pintype "passive"))
    )
    (net (code "78") (name "unconnected-(J4-Pad20)") (class "Default")
      (node (ref "J4") (pin "20") (pinfunction "20_20") (pintype "passive"))
    )
    (net (code "79") (name "unconnected-(U5-NC-Pad8)") (class "Default")
      (node (ref "U5") (pin "8") (pinfunction "NC_8") (pintype "passive"))
    )
    (net (code "80") (name "unconnected-(U5-NC-Pad19)") (class "Default")
      (node (ref "U5") (pin "19") (pinfunction "NC_19") (pintype "passive"))
    )
    (net (code "81") (name "unconnected-(U12-Y3M-Pad38)") (class "Default")
      (node (ref "U12") (pin "38") (pinfunction "Y3M_38") (pintype "passive"))
    )
    (net (code "82") (name "unconnected-(U12-Y3P-Pad37)") (class "Default")
      (node (ref "U12") (pin "37") (pinfunction "Y3P_37") (pintype "passive"))
    )
  )
)
